# control_board.net
KiCad netlist of a schematic drawn in EAGLE
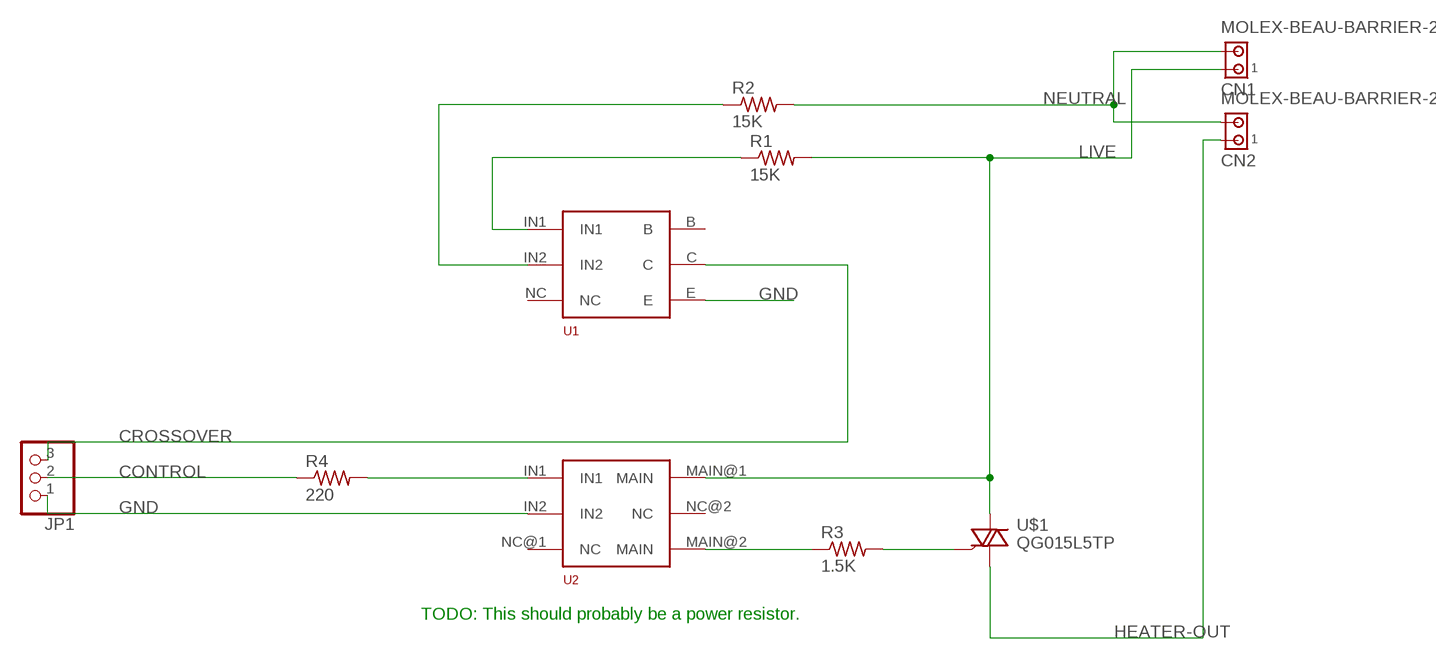
[diagram p0: schematic, sheet 1]

(export (version "E")
  (design (tool "Eeschema 10.0.6"))
  (components
    (comp (ref "CN1")
      (value "MOLEX-BEAU-BARRIER-2")
      (footprint "eagle-import:MOLEX-BEAU-BARRIER-2")
      (libsource (lib "eagle-import") (part "MOLEX-BEAU-BARRIER-2"))
    )
    (comp (ref "CN2")
      (value "MOLEX-BEAU-BARRIER-2")
      (footprint "eagle-import:MOLEX-BEAU-BARRIER-2")
      (libsource (lib "eagle-import") (part "MOLEX-BEAU-BARRIER-2"))
    )
    (comp (ref "JP1")
      (value "PINHD-1X3/90")
      (footprint "eagle-import:1X03_90")
      (libsource (lib "eagle-import") (part "PINHD-1X3/90"))
    )
    (comp (ref "R1")
      (value "15K")
      (footprint "eagle-import:RSF100")
      (libsource (lib "eagle-import") (part "RSF100JB-73"))
    )
    (comp (ref "R2")
      (value "15K")
      (footprint "eagle-import:RSF100")
      (libsource (lib "eagle-import") (part "RSF100JB-73"))
    )
    (comp (ref "R3")
      (value "1.5K")
      (footprint "eagle-import:CR-25")
      (libsource (lib "eagle-import") (part "YAGEO_CFR"))
    )
    (comp (ref "R4")
      (value "220")
      (footprint "eagle-import:CR-25")
      (libsource (lib "eagle-import") (part "YAGEO_CFR"))
    )
    (comp (ref "U$1")
      (value "QG015L5TP")
      (footprint "eagle-import:QG015L5TP")
      (libsource (lib "eagle-import") (part "QG015L5TP"))
    )
    (comp (ref "U1")
      (value "H11AA4M")
      (footprint "eagle-import:H11AA4M")
      (libsource (lib "eagle-import") (part "H11AA4M"))
    )
    (comp (ref "U2")
      (value "MOC3052M")
      (footprint "eagle-import:MOC3052M")
      (libsource (lib "eagle-import") (part "MOC3052M"))
    )
  )
  (nets
    (net (code "1") (name "/CONTROL") (class "Default")
      (node (ref "JP1") (pin "2") (pinfunction "2_2") (pintype "passive"))
      (node (ref "R4") (pin "P$1") (pinfunction "1_P$1") (pintype "passive"))
    )
    (net (code "2") (name "/CROSSOVER") (class "Default")
      (node (ref "JP1") (pin "3") (pinfunction "3_3") (pintype "passive"))
      (node (ref "U1") (pin "C") (pinfunction "C_C") (pintype "bidirectional"))
    )
    (net (code "3") (name "/GND") (class "Default")
      (node (ref "JP1") (pin "1") (pinfunction "1_1") (pintype "passive"))
      (node (ref "U1") (pin "E") (pinfunction "E_E") (pintype "bidirectional"))
      (node (ref "U2") (pin "IN2") (pinfunction "IN2_IN2") (pintype "passive"))
    )
    (net (code "4") (name "/HEATER-OUT") (class "Default")
      (node (ref "CN2") (pin "P1") (pinfunction "1_P1") (pintype "passive"))
      (node (ref "U$1") (pin "P$1") (pinfunction "A1_P$1") (pintype "passive"))
    )
    (net (code "5") (name "/LIVE") (class "Default")
      (node (ref "CN1") (pin "P1") (pinfunction "1_P1") (pintype "passive"))
      (node (ref "R1") (pin "P$2") (pinfunction "2_P$2") (pintype "passive"))
      (node (ref "U$1") (pin "P$3") (pinfunction "A2_P$3") (pintype "passive"))
      (node (ref "U2") (pin "MAIN@1") (pinfunction "MAIN_MAIN@1") (pintype "bidirectional"))
    )
    (net (code "6") (name "/NEUTRAL") (class "Default")
      (node (ref "CN1") (pin "P2") (pinfunction "2_P2") (pintype "passive"))
      (node (ref "CN2") (pin "P2") (pinfunction "2_P2") (pintype "passive"))
      (node (ref "R2") (pin "P$2") (pinfunction "2_P$2") (pintype "passive"))
    )
    (net (code "7") (name "Net-(R1-1)") (class "Default")
      (node (ref "R1") (pin "P$1") (pinfunction "1_P$1") (pintype "passive"))
      (node (ref "U1") (pin "IN1") (pinfunction "IN1_IN1") (pintype "passive"))
    )
    (net (code "8") (name "Net-(R2-1)") (class "Default")
      (node (ref "R2") (pin "P$1") (pinfunction "1_P$1") (pintype "passive"))
      (node (ref "U1") (pin "IN2") (pinfunction "IN2_IN2") (pintype "passive"))
    )
    (net (code "9") (name "Net-(R3-1)") (class "Default")
      (node (ref "R3") (pin "P$1") (pinfunction "1_P$1") (pintype "passive"))
      (node (ref "U2") (pin "MAIN@2") (pinfunction "MAIN_MAIN@2") (pintype "bidirectional"))
    )
    (net (code "10") (name "Net-(R3-2)") (class "Default")
      (node (ref "R3") (pin "P$2") (pinfunction "2_P$2") (pintype "passive"))
      (node (ref "U$1") (pin "P$2") (pinfunction "G_P$2") (pintype "passive"))
    )
    (net (code "11") (name "Net-(R4-2)") (class "Default")
      (node (ref "R4") (pin "P$2") (pinfunction "2_P$2") (pintype "passive"))
      (node (ref "U2") (pin "IN1") (pinfunction "IN1_IN1") (pintype "passive"))
    )
    (net (code "12") (name "unconnected-(U1-PadB)") (class "Default")
      (node (ref "U1") (pin "B") (pinfunction "B_B") (pintype "bidirectional"))
    )
    (net (code "13") (name "unconnected-(U1-PadNC)") (class "Default")
      (node (ref "U1") (pin "NC") (pinfunction "NC_NC") (pintype "no_connect"))
    )
    (net (code "14") (name "unconnected-(U2-NC-PadNC@1)") (class "Default")
      (node (ref "U2") (pin "NC@1") (pinfunction "NC_NC@1") (pintype "no_connect"))
    )
    (net (code "15") (name "unconnected-(U2-NC-PadNC@2)") (class "Default")
      (node (ref "U2") (pin "NC@2") (pinfunction "NC_NC@2") (pintype "no_connect"))
    )
  )
)
